# flipper-coleco.net
KiCad netlist of a schematic drawn in EAGLE
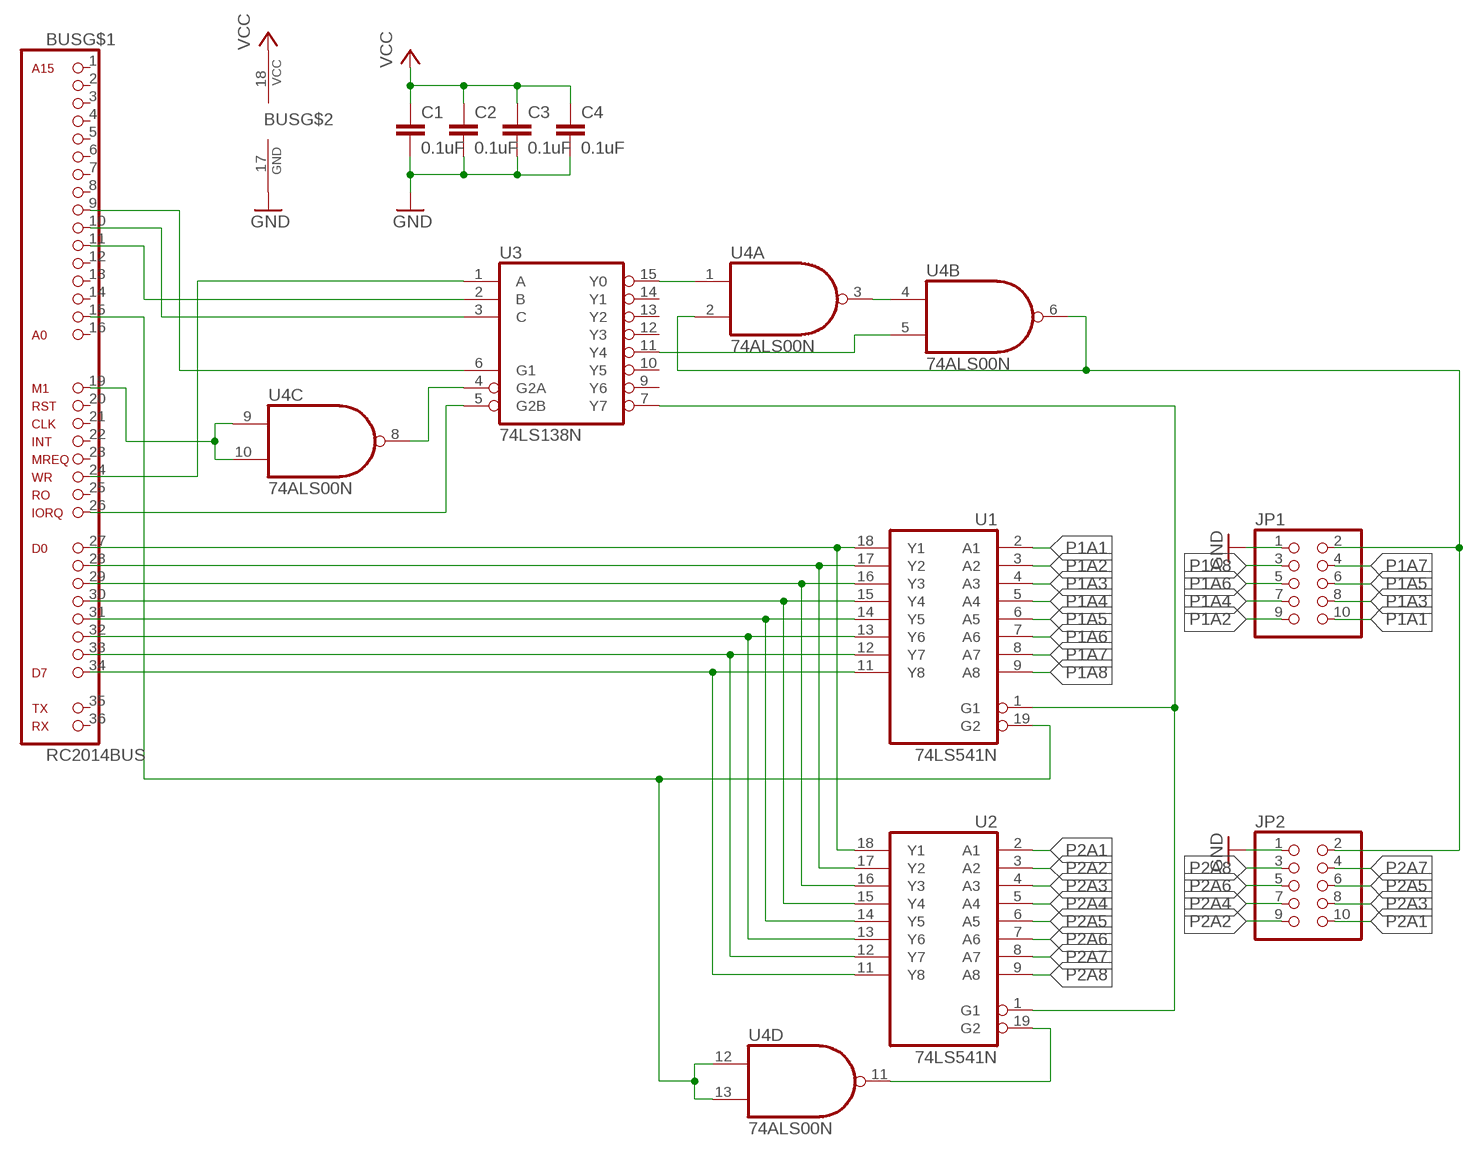
[diagram p0: schematic, sheet 1]

(export (version "E")
  (design (tool "Eeschema 10.0.6"))
  (components
    (comp (ref "BUS")
      (value "RC2014BUS")
      (footprint "eagle-import:1X39")
      (libsource (lib "eagle-import") (part "RC2014BUS"))
    )
    (comp (ref "C1")
      (value "0.1uF")
      (footprint "eagle-import:C050-024X044")
      (libsource (lib "eagle-import") (part "C-EU050-024X044"))
    )
    (comp (ref "C2")
      (value "0.1uF")
      (footprint "eagle-import:C050-024X044")
      (libsource (lib "eagle-import") (part "C-EU050-024X044"))
    )
    (comp (ref "C3")
      (value "0.1uF")
      (footprint "eagle-import:C050-024X044")
      (libsource (lib "eagle-import") (part "C-EU050-024X044"))
    )
    (comp (ref "C4")
      (value "0.1uF")
      (footprint "eagle-import:C050-024X044")
      (libsource (lib "eagle-import") (part "C-EU050-024X044"))
    )
    (comp (ref "JP1")
      (value "PINHD-2X5")
      (footprint "eagle-import:2X05")
      (libsource (lib "eagle-import") (part "PINHD-2X5"))
    )
    (comp (ref "JP2")
      (value "PINHD-2X5")
      (footprint "eagle-import:2X05")
      (libsource (lib "eagle-import") (part "PINHD-2X5"))
    )
    (comp (ref "U1")
      (value "74LS541N")
      (footprint "eagle-import:DIL20")
      (libsource (lib "eagle-import") (part "74541NLS"))
    )
    (comp (ref "U2")
      (value "74LS541N")
      (footprint "eagle-import:DIL20")
      (libsource (lib "eagle-import") (part "74541NLS"))
    )
    (comp (ref "U3")
      (value "74LS138N")
      (footprint "eagle-import:DIL16")
      (libsource (lib "eagle-import") (part "74138NLS"))
    )
    (comp (ref "U4")
      (value "74ALS00N")
      (footprint "eagle-import:DIL14")
      (libsource (lib "eagle-import") (part "7400NALS"))
    )
  )
  (nets
    (net (code "1") (name "GND") (class "Default")
      (node (ref "BUS") (pin "17") (pinfunction "GND_17") (pintype "power_in"))
      (node (ref "C1") (pin "2") (pinfunction "2_2") (pintype "passive"))
      (node (ref "C2") (pin "2") (pinfunction "2_2") (pintype "passive"))
      (node (ref "C3") (pin "2") (pinfunction "2_2") (pintype "passive"))
      (node (ref "C4") (pin "2") (pinfunction "2_2") (pintype "passive"))
      (node (ref "JP1") (pin "1") (pinfunction "1_1") (pintype "passive"))
      (node (ref "JP2") (pin "1") (pinfunction "1_1") (pintype "passive"))
    )
    (net (code "2") (name "Net-(BUSA-A1)") (class "Default")
      (node (ref "BUS") (pin "15") (pinfunction "A1_15") (pintype "passive"))
      (node (ref "U1") (pin "19") (pinfunction "G2_19") (pintype "input"))
      (node (ref "U4") (pin "12") (pinfunction "I0_12") (pintype "input"))
      (node (ref "U4") (pin "13") (pinfunction "I1_13") (pintype "input"))
    )
    (net (code "3") (name "Net-(BUSA-A5)") (class "Default")
      (node (ref "BUS") (pin "11") (pinfunction "A5_11") (pintype "passive"))
      (node (ref "U3") (pin "2") (pinfunction "B_2") (pintype "input"))
    )
    (net (code "4") (name "Net-(BUSA-A6)") (class "Default")
      (node (ref "BUS") (pin "10") (pinfunction "A6_10") (pintype "passive"))
      (node (ref "U3") (pin "3") (pinfunction "C_3") (pintype "input"))
    )
    (net (code "5") (name "Net-(BUSA-A7)") (class "Default")
      (node (ref "BUS") (pin "9") (pinfunction "A7_9") (pintype "passive"))
      (node (ref "U3") (pin "6") (pinfunction "G1_6") (pintype "input"))
    )
    (net (code "6") (name "Net-(BUSA-D0)") (class "Default")
      (node (ref "BUS") (pin "27") (pinfunction "D0_27") (pintype "passive"))
      (node (ref "U1") (pin "18") (pinfunction "Y1_18") (pintype "tri_state"))
      (node (ref "U2") (pin "18") (pinfunction "Y1_18") (pintype "tri_state"))
    )
    (net (code "7") (name "Net-(BUSA-D1)") (class "Default")
      (node (ref "BUS") (pin "28") (pinfunction "D1_28") (pintype "passive"))
      (node (ref "U1") (pin "17") (pinfunction "Y2_17") (pintype "tri_state"))
      (node (ref "U2") (pin "17") (pinfunction "Y2_17") (pintype "tri_state"))
    )
    (net (code "8") (name "Net-(BUSA-D2)") (class "Default")
      (node (ref "BUS") (pin "29") (pinfunction "D2_29") (pintype "passive"))
      (node (ref "U1") (pin "16") (pinfunction "Y3_16") (pintype "tri_state"))
      (node (ref "U2") (pin "16") (pinfunction "Y3_16") (pintype "tri_state"))
    )
    (net (code "9") (name "Net-(BUSA-D3)") (class "Default")
      (node (ref "BUS") (pin "30") (pinfunction "D3_30") (pintype "passive"))
      (node (ref "U1") (pin "15") (pinfunction "Y4_15") (pintype "tri_state"))
      (node (ref "U2") (pin "15") (pinfunction "Y4_15") (pintype "tri_state"))
    )
    (net (code "10") (name "Net-(BUSA-D4)") (class "Default")
      (node (ref "BUS") (pin "31") (pinfunction "D4_31") (pintype "passive"))
      (node (ref "U1") (pin "14") (pinfunction "Y5_14") (pintype "tri_state"))
      (node (ref "U2") (pin "14") (pinfunction "Y5_14") (pintype "tri_state"))
    )
    (net (code "11") (name "Net-(BUSA-D5)") (class "Default")
      (node (ref "BUS") (pin "32") (pinfunction "D5_32") (pintype "passive"))
      (node (ref "U1") (pin "13") (pinfunction "Y6_13") (pintype "tri_state"))
      (node (ref "U2") (pin "13") (pinfunction "Y6_13") (pintype "tri_state"))
    )
    (net (code "12") (name "Net-(BUSA-D6)") (class "Default")
      (node (ref "BUS") (pin "33") (pinfunction "D6_33") (pintype "passive"))
      (node (ref "U1") (pin "12") (pinfunction "Y7_12") (pintype "tri_state"))
      (node (ref "U2") (pin "12") (pinfunction "Y7_12") (pintype "tri_state"))
    )
    (net (code "13") (name "Net-(BUSA-D7)") (class "Default")
      (node (ref "BUS") (pin "34") (pinfunction "D7_34") (pintype "passive"))
      (node (ref "U1") (pin "11") (pinfunction "Y8_11") (pintype "tri_state"))
      (node (ref "U2") (pin "11") (pinfunction "Y8_11") (pintype "tri_state"))
    )
    (net (code "14") (name "Net-(BUSA-IORQ)") (class "Default")
      (node (ref "BUS") (pin "26") (pinfunction "IORQ_26") (pintype "passive"))
      (node (ref "U3") (pin "5") (pinfunction "G2B_5") (pintype "input"))
    )
    (net (code "15") (name "Net-(BUSA-M1)") (class "Default")
      (node (ref "BUS") (pin "19") (pinfunction "M1_19") (pintype "passive"))
      (node (ref "U4") (pin "10") (pinfunction "I1_10") (pintype "input"))
      (node (ref "U4") (pin "9") (pinfunction "I0_9") (pintype "input"))
    )
    (net (code "16") (name "Net-(BUSA-WR)") (class "Default")
      (node (ref "BUS") (pin "24") (pinfunction "WR_24") (pintype "passive"))
      (node (ref "U3") (pin "1") (pinfunction "A_1") (pintype "input"))
    )
    (net (code "17") (name "Net-(U1A-G1)") (class "Default")
      (node (ref "U1") (pin "1") (pinfunction "G1_1") (pintype "input"))
      (node (ref "U2") (pin "1") (pinfunction "G1_1") (pintype "input"))
      (node (ref "U3") (pin "7") (pinfunction "Y7_7") (pintype "output"))
    )
    (net (code "18") (name "Net-(U2A-G2)") (class "Default")
      (node (ref "U2") (pin "19") (pinfunction "G2_19") (pintype "input"))
      (node (ref "U4") (pin "11") (pinfunction "O_11") (pintype "output"))
    )
    (net (code "19") (name "Net-(U3A-G2A)") (class "Default")
      (node (ref "U3") (pin "4") (pinfunction "G2A_4") (pintype "input"))
      (node (ref "U4") (pin "8") (pinfunction "O_8") (pintype "output"))
    )
    (net (code "20") (name "Net-(U3A-Y0)") (class "Default")
      (node (ref "U3") (pin "15") (pinfunction "Y0_15") (pintype "output"))
      (node (ref "U4") (pin "1") (pinfunction "I0_1") (pintype "input"))
    )
    (net (code "21") (name "Net-(U3A-Y4)") (class "Default")
      (node (ref "U3") (pin "11") (pinfunction "Y4_11") (pintype "output"))
      (node (ref "U4") (pin "5") (pinfunction "I1_5") (pintype "input"))
    )
    (net (code "22") (name "Net-(U4A-I1)") (class "Default")
      (node (ref "JP1") (pin "2") (pinfunction "2_2") (pintype "passive"))
      (node (ref "JP2") (pin "2") (pinfunction "2_2") (pintype "passive"))
      (node (ref "U4") (pin "2") (pinfunction "I1_2") (pintype "input"))
      (node (ref "U4") (pin "6") (pinfunction "O_6") (pintype "output"))
    )
    (net (code "23") (name "Net-(U4A-O)") (class "Default")
      (node (ref "U4") (pin "3") (pinfunction "O_3") (pintype "output"))
      (node (ref "U4") (pin "4") (pinfunction "I0_4") (pintype "input"))
    )
    (net (code "24") (name "P1A1") (class "Default")
      (node (ref "JP1") (pin "10") (pinfunction "10_10") (pintype "passive"))
      (node (ref "U1") (pin "2") (pinfunction "A1_2") (pintype "input"))
    )
    (net (code "25") (name "P1A2") (class "Default")
      (node (ref "JP1") (pin "9") (pinfunction "9_9") (pintype "passive"))
      (node (ref "U1") (pin "3") (pinfunction "A2_3") (pintype "input"))
    )
    (net (code "26") (name "P1A3") (class "Default")
      (node (ref "JP1") (pin "8") (pinfunction "8_8") (pintype "passive"))
      (node (ref "U1") (pin "4") (pinfunction "A3_4") (pintype "input"))
    )
    (net (code "27") (name "P1A4") (class "Default")
      (node (ref "JP1") (pin "7") (pinfunction "7_7") (pintype "passive"))
      (node (ref "U1") (pin "5") (pinfunction "A4_5") (pintype "input"))
    )
    (net (code "28") (name "P1A5") (class "Default")
      (node (ref "JP1") (pin "6") (pinfunction "6_6") (pintype "passive"))
      (node (ref "U1") (pin "6") (pinfunction "A5_6") (pintype "input"))
    )
    (net (code "29") (name "P1A6") (class "Default")
      (node (ref "JP1") (pin "5") (pinfunction "5_5") (pintype "passive"))
      (node (ref "U1") (pin "7") (pinfunction "A6_7") (pintype "input"))
    )
    (net (code "30") (name "P1A7") (class "Default")
      (node (ref "JP1") (pin "4") (pinfunction "4_4") (pintype "passive"))
      (node (ref "U1") (pin "8") (pinfunction "A7_8") (pintype "input"))
    )
    (net (code "31") (name "P1A8") (class "Default")
      (node (ref "JP1") (pin "3") (pinfunction "3_3") (pintype "passive"))
      (node (ref "U1") (pin "9") (pinfunction "A8_9") (pintype "input"))
    )
    (net (code "32") (name "P2A1") (class "Default")
      (node (ref "JP2") (pin "10") (pinfunction "10_10") (pintype "passive"))
      (node (ref "U2") (pin "2") (pinfunction "A1_2") (pintype "input"))
    )
    (net (code "33") (name "P2A2") (class "Default")
      (node (ref "JP2") (pin "9") (pinfunction "9_9") (pintype "passive"))
      (node (ref "U2") (pin "3") (pinfunction "A2_3") (pintype "input"))
    )
    (net (code "34") (name "P2A3") (class "Default")
      (node (ref "JP2") (pin "8") (pinfunction "8_8") (pintype "passive"))
      (node (ref "U2") (pin "4") (pinfunction "A3_4") (pintype "input"))
    )
    (net (code "35") (name "P2A4") (class "Default")
      (node (ref "JP2") (pin "7") (pinfunction "7_7") (pintype "passive"))
      (node (ref "U2") (pin "5") (pinfunction "A4_5") (pintype "input"))
    )
    (net (code "36") (name "P2A5") (class "Default")
      (node (ref "JP2") (pin "6") (pinfunction "6_6") (pintype "passive"))
      (node (ref "U2") (pin "6") (pinfunction "A5_6") (pintype "input"))
    )
    (net (code "37") (name "P2A6") (class "Default")
      (node (ref "JP2") (pin "5") (pinfunction "5_5") (pintype "passive"))
      (node (ref "U2") (pin "7") (pinfunction "A6_7") (pintype "input"))
    )
    (net (code "38") (name "P2A7") (class "Default")
      (node (ref "JP2") (pin "4") (pinfunction "4_4") (pintype "passive"))
      (node (ref "U2") (pin "8") (pinfunction "A7_8") (pintype "input"))
    )
    (net (code "39") (name "P2A8") (class "Default")
      (node (ref "JP2") (pin "3") (pinfunction "3_3") (pintype "passive"))
      (node (ref "U2") (pin "9") (pinfunction "A8_9") (pintype "input"))
    )
    (net (code "40") (name "VCC") (class "Default")
      (node (ref "BUS") (pin "18") (pinfunction "VCC_18") (pintype "power_in"))
      (node (ref "C1") (pin "1") (pinfunction "1_1") (pintype "passive"))
      (node (ref "C2") (pin "1") (pinfunction "1_1") (pintype "passive"))
      (node (ref "C3") (pin "1") (pinfunction "1_1") (pintype "passive"))
      (node (ref "C4") (pin "1") (pinfunction "1_1") (pintype "passive"))
    )
    (net (code "41") (name "unconnected-(BUSA-A0-Pad16)") (class "Default")
      (node (ref "BUS") (pin "16") (pinfunction "A0_16") (pintype "passive"))
    )
    (net (code "42") (name "unconnected-(BUSA-A2-Pad14)") (class "Default")
      (node (ref "BUS") (pin "14") (pinfunction "A2_14") (pintype "passive"))
    )
    (net (code "43") (name "unconnected-(BUSA-A3-Pad13)") (class "Default")
      (node (ref "BUS") (pin "13") (pinfunction "A3_13") (pintype "passive"))
    )
    (net (code "44") (name "unconnected-(BUSA-A4-Pad12)") (class "Default")
      (node (ref "BUS") (pin "12") (pinfunction "A4_12") (pintype "passive"))
    )
    (net (code "45") (name "unconnected-(BUSA-A8-Pad8)") (class "Default")
      (node (ref "BUS") (pin "8") (pinfunction "A8_8") (pintype "passive"))
    )
    (net (code "46") (name "unconnected-(BUSA-A9-Pad7)") (class "Default")
      (node (ref "BUS") (pin "7") (pinfunction "A9_7") (pintype "passive"))
    )
    (net (code "47") (name "unconnected-(BUSA-A10-Pad6)") (class "Default")
      (node (ref "BUS") (pin "6") (pinfunction "A10_6") (pintype "passive"))
    )
    (net (code "48") (name "unconnected-(BUSA-A11-Pad5)") (class "Default")
      (node (ref "BUS") (pin "5") (pinfunction "A11_5") (pintype "passive"))
    )
    (net (code "49") (name "unconnected-(BUSA-A12-Pad4)") (class "Default")
      (node (ref "BUS") (pin "4") (pinfunction "A12_4") (pintype "passive"))
    )
    (net (code "50") (name "unconnected-(BUSA-A13-Pad3)") (class "Default")
      (node (ref "BUS") (pin "3") (pinfunction "A13_3") (pintype "passive"))
    )
    (net (code "51") (name "unconnected-(BUSA-A14-Pad2)") (class "Default")
      (node (ref "BUS") (pin "2") (pinfunction "A14_2") (pintype "passive"))
    )
    (net (code "52") (name "unconnected-(BUSA-A15-Pad1)") (class "Default")
      (node (ref "BUS") (pin "1") (pinfunction "A15_1") (pintype "passive"))
    )
    (net (code "53") (name "unconnected-(BUSA-CLK-Pad21)") (class "Default")
      (node (ref "BUS") (pin "21") (pinfunction "CLK_21") (pintype "passive"))
    )
    (net (code "54") (name "unconnected-(BUSA-INT-Pad22)") (class "Default")
      (node (ref "BUS") (pin "22") (pinfunction "INT_22") (pintype "passive"))
    )
    (net (code "55") (name "unconnected-(BUSA-MREQ-Pad23)") (class "Default")
      (node (ref "BUS") (pin "23") (pinfunction "MREQ_23") (pintype "passive"))
    )
    (net (code "56") (name "unconnected-(BUSA-RO-Pad25)") (class "Default")
      (node (ref "BUS") (pin "25") (pinfunction "RO_25") (pintype "passive"))
    )
    (net (code "57") (name "unconnected-(BUSA-RST-Pad20)") (class "Default")
      (node (ref "BUS") (pin "20") (pinfunction "RST_20") (pintype "passive"))
    )
    (net (code "58") (name "unconnected-(BUSA-RX-Pad36)") (class "Default")
      (node (ref "BUS") (pin "36") (pinfunction "RX_36") (pintype "passive"))
    )
    (net (code "59") (name "unconnected-(BUSA-TX-Pad35)") (class "Default")
      (node (ref "BUS") (pin "35") (pinfunction "TX_35") (pintype "passive"))
    )
    (net (code "60") (name "unconnected-(U3A-Y1-Pad14)") (class "Default")
      (node (ref "U3") (pin "14") (pinfunction "Y1_14") (pintype "output"))
    )
    (net (code "61") (name "unconnected-(U3A-Y2-Pad13)") (class "Default")
      (node (ref "U3") (pin "13") (pinfunction "Y2_13") (pintype "output"))
    )
    (net (code "62") (name "unconnected-(U3A-Y3-Pad12)") (class "Default")
      (node (ref "U3") (pin "12") (pinfunction "Y3_12") (pintype "output"))
    )
    (net (code "63") (name "unconnected-(U3A-Y5-Pad10)") (class "Default")
      (node (ref "U3") (pin "10") (pinfunction "Y5_10") (pintype "output"))
    )
    (net (code "64") (name "unconnected-(U3A-Y6-Pad9)") (class "Default")
      (node (ref "U3") (pin "9") (pinfunction "Y6_9") (pintype "output"))
    )
  )
)
